# 03_SHIELD_SLOT_A.net
KiCad netlist of a schematic drawn in Altium Designer
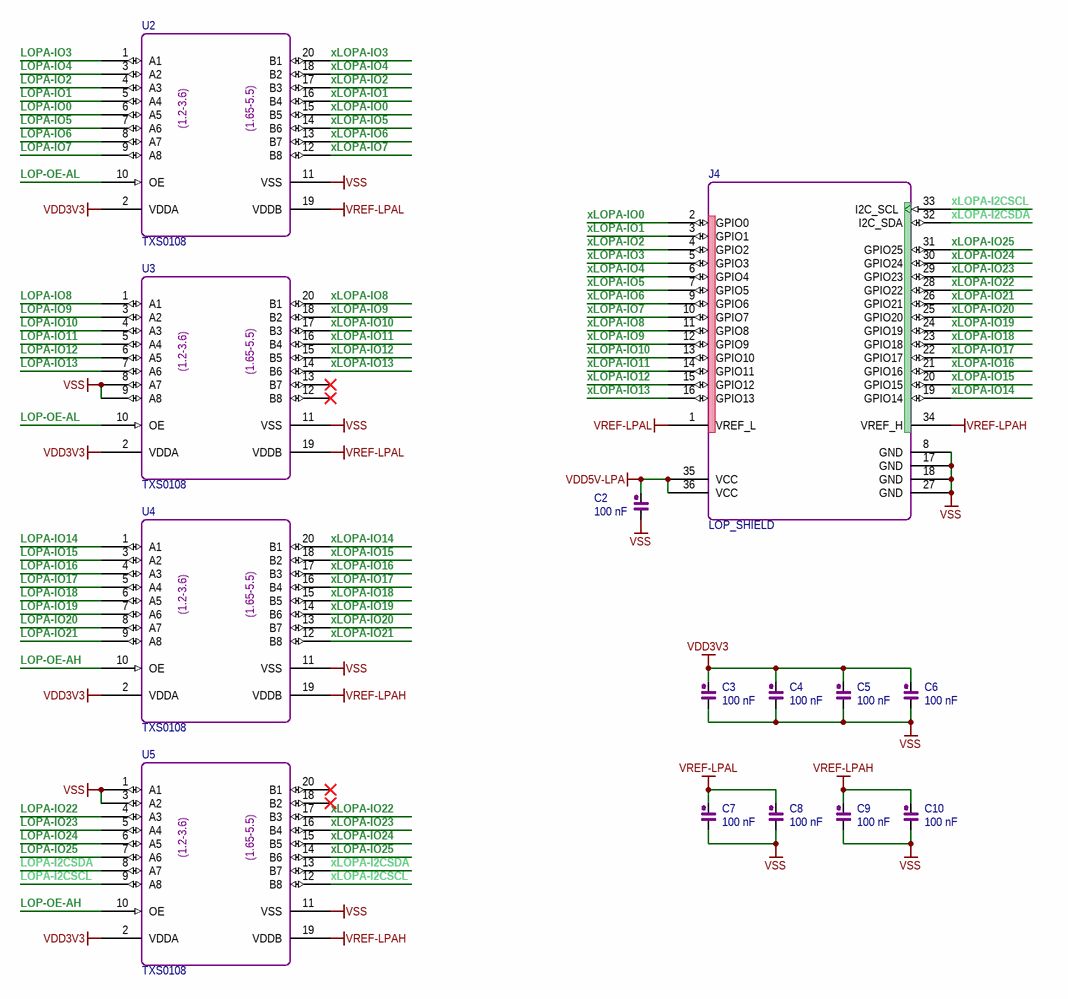
[diagram p0: 03_SHIELD_SLOT_A.SchDoc]

(export (version "E")
  (design (tool "Eeschema 10.0.6"))
  (components
    (comp (ref "C2")
      (value "100 nF")
      (footprint "0603A1")
      (description "Normal Capacitor")
      (fields
        (field (name "PARTNUMBER") "0")
        (field (name "PUBLISHER") "Cowin")
        (field (name "DESIGNER") "shyul")
      )
      (libsource (lib "Basc_1_Passive") (part "CAP"))
    )
    (comp (ref "C3")
      (value "100 nF")
      (footprint "0603A1")
      (description "Normal Capacitor")
      (fields
        (field (name "PARTNUMBER") "0")
        (field (name "PUBLISHER") "Cowin")
        (field (name "DESIGNER") "shyul")
      )
      (libsource (lib "Basc_1_Passive") (part "CAP"))
    )
    (comp (ref "C4")
      (value "100 nF")
      (footprint "0603A1")
      (description "Normal Capacitor")
      (fields
        (field (name "PARTNUMBER") "0")
        (field (name "PUBLISHER") "Cowin")
        (field (name "DESIGNER") "shyul")
      )
      (libsource (lib "Basc_1_Passive") (part "CAP"))
    )
    (comp (ref "C5")
      (value "100 nF")
      (footprint "0603A1")
      (description "Normal Capacitor")
      (fields
        (field (name "PARTNUMBER") "0")
        (field (name "PUBLISHER") "Cowin")
        (field (name "DESIGNER") "shyul")
      )
      (libsource (lib "Basc_1_Passive") (part "CAP"))
    )
    (comp (ref "C6")
      (value "100 nF")
      (footprint "0603A1")
      (description "Normal Capacitor")
      (fields
        (field (name "PARTNUMBER") "0")
        (field (name "PUBLISHER") "Cowin")
        (field (name "DESIGNER") "shyul")
      )
      (libsource (lib "Basc_1_Passive") (part "CAP"))
    )
    (comp (ref "C7")
      (value "100 nF")
      (footprint "0603A1")
      (description "Normal Capacitor")
      (fields
        (field (name "PARTNUMBER") "0")
        (field (name "PUBLISHER") "Cowin")
        (field (name "DESIGNER") "shyul")
      )
      (libsource (lib "Basc_1_Passive") (part "CAP"))
    )
    (comp (ref "C8")
      (value "100 nF")
      (footprint "0603A1")
      (description "Normal Capacitor")
      (fields
        (field (name "PARTNUMBER") "0")
        (field (name "PUBLISHER") "Cowin")
        (field (name "DESIGNER") "shyul")
      )
      (libsource (lib "Basc_1_Passive") (part "CAP"))
    )
    (comp (ref "C9")
      (value "100 nF")
      (footprint "0603A1")
      (description "Normal Capacitor")
      (fields
        (field (name "PARTNUMBER") "0")
        (field (name "PUBLISHER") "Cowin")
        (field (name "DESIGNER") "shyul")
      )
      (libsource (lib "Basc_1_Passive") (part "CAP"))
    )
    (comp (ref "C10")
      (value "100 nF")
      (footprint "0603A1")
      (description "Normal Capacitor")
      (fields
        (field (name "PARTNUMBER") "0")
        (field (name "PUBLISHER") "Cowin")
        (field (name "DESIGNER") "shyul")
      )
      (libsource (lib "Basc_1_Passive") (part "CAP"))
    )
    (comp (ref "J4")
      (value "LOP_SHIELD")
      (footprint "LOP_SHIELD")
      (description "Lophilo Shield Module Slot")
      (fields (field (name "PUBLISHER") "Cowin") (field (name "DESIGNER") "shyul"))
      (libsource (lib "PCB_LDB-U01") (part "LOP_SHIELD"))
    )
    (comp (ref "U2")
      (value "TXS0108")
      (footprint "TSSOP-20")
      (description "8-bit Translator")
      (fields (field (name "DESIGNER") "shyul") (field (name "PUBLISHER") "Cowin"))
      (libsource (lib "IC_01_Logic") (part "TXS0108"))
    )
    (comp (ref "U3")
      (value "TXS0108")
      (footprint "TSSOP-20")
      (description "8-bit Translator")
      (fields (field (name "DESIGNER") "shyul") (field (name "PUBLISHER") "Cowin"))
      (libsource (lib "IC_01_Logic") (part "TXS0108"))
    )
    (comp (ref "U4")
      (value "TXS0108")
      (footprint "TSSOP-20")
      (description "8-bit Translator")
      (fields (field (name "DESIGNER") "shyul") (field (name "PUBLISHER") "Cowin"))
      (libsource (lib "IC_01_Logic") (part "TXS0108"))
    )
    (comp (ref "U5")
      (value "TXS0108")
      (footprint "TSSOP-20")
      (description "8-bit Translator")
      (fields (field (name "DESIGNER") "shyul") (field (name "PUBLISHER") "Cowin"))
      (libsource (lib "IC_01_Logic") (part "TXS0108"))
    )
  )
  (nets
    (net (code "1") (name "/LOP-OE-AH") (class "Default")
      (node (ref "U4") (pin "10") (pinfunction "OE_10") (pintype "input"))
      (node (ref "U5") (pin "10") (pinfunction "OE_10") (pintype "input"))
    )
    (net (code "2") (name "/LOP-OE-AL") (class "Default")
      (node (ref "U2") (pin "10") (pinfunction "OE_10") (pintype "input"))
      (node (ref "U3") (pin "10") (pinfunction "OE_10") (pintype "input"))
    )
    (net (code "3") (name "/LOPA-I2CSCL") (class "Default")
      (node (ref "U5") (pin "9") (pinfunction "A8_9") (pintype "bidirectional"))
    )
    (net (code "4") (name "/LOPA-I2CSDA") (class "Default")
      (node (ref "U5") (pin "8") (pinfunction "A7_8") (pintype "bidirectional"))
    )
    (net (code "5") (name "/LOPA-IO0") (class "Default")
      (node (ref "U2") (pin "6") (pinfunction "A5_6") (pintype "bidirectional"))
    )
    (net (code "6") (name "/LOPA-IO1") (class "Default")
      (node (ref "U2") (pin "5") (pinfunction "A4_5") (pintype "bidirectional"))
    )
    (net (code "7") (name "/LOPA-IO2") (class "Default")
      (node (ref "U2") (pin "4") (pinfunction "A3_4") (pintype "bidirectional"))
    )
    (net (code "8") (name "/LOPA-IO3") (class "Default")
      (node (ref "U2") (pin "1") (pinfunction "A1_1") (pintype "bidirectional"))
    )
    (net (code "9") (name "/LOPA-IO4") (class "Default")
      (node (ref "U2") (pin "3") (pinfunction "A2_3") (pintype "bidirectional"))
    )
    (net (code "10") (name "/LOPA-IO5") (class "Default")
      (node (ref "U2") (pin "7") (pinfunction "A6_7") (pintype "bidirectional"))
    )
    (net (code "11") (name "/LOPA-IO6") (class "Default")
      (node (ref "U2") (pin "8") (pinfunction "A7_8") (pintype "bidirectional"))
    )
    (net (code "12") (name "/LOPA-IO7") (class "Default")
      (node (ref "U2") (pin "9") (pinfunction "A8_9") (pintype "bidirectional"))
    )
    (net (code "13") (name "/LOPA-IO8") (class "Default")
      (node (ref "U3") (pin "1") (pinfunction "A1_1") (pintype "bidirectional"))
    )
    (net (code "14") (name "/LOPA-IO9") (class "Default")
      (node (ref "U3") (pin "3") (pinfunction "A2_3") (pintype "bidirectional"))
    )
    (net (code "15") (name "/LOPA-IO10") (class "Default")
      (node (ref "U3") (pin "4") (pinfunction "A3_4") (pintype "bidirectional"))
    )
    (net (code "16") (name "/LOPA-IO11") (class "Default")
      (node (ref "U3") (pin "5") (pinfunction "A4_5") (pintype "bidirectional"))
    )
    (net (code "17") (name "/LOPA-IO12") (class "Default")
      (node (ref "U3") (pin "6") (pinfunction "A5_6") (pintype "bidirectional"))
    )
    (net (code "18") (name "/LOPA-IO13") (class "Default")
      (node (ref "U3") (pin "7") (pinfunction "A6_7") (pintype "bidirectional"))
    )
    (net (code "19") (name "/LOPA-IO14") (class "Default")
      (node (ref "U4") (pin "1") (pinfunction "A1_1") (pintype "bidirectional"))
    )
    (net (code "20") (name "/LOPA-IO15") (class "Default")
      (node (ref "U4") (pin "3") (pinfunction "A2_3") (pintype "bidirectional"))
    )
    (net (code "21") (name "/LOPA-IO16") (class "Default")
      (node (ref "U4") (pin "4") (pinfunction "A3_4") (pintype "bidirectional"))
    )
    (net (code "22") (name "/LOPA-IO17") (class "Default")
      (node (ref "U4") (pin "5") (pinfunction "A4_5") (pintype "bidirectional"))
    )
    (net (code "23") (name "/LOPA-IO18") (class "Default")
      (node (ref "U4") (pin "6") (pinfunction "A5_6") (pintype "bidirectional"))
    )
    (net (code "24") (name "/LOPA-IO19") (class "Default")
      (node (ref "U4") (pin "7") (pinfunction "A6_7") (pintype "bidirectional"))
    )
    (net (code "25") (name "/LOPA-IO20") (class "Default")
      (node (ref "U4") (pin "8") (pinfunction "A7_8") (pintype "bidirectional"))
    )
    (net (code "26") (name "/LOPA-IO21") (class "Default")
      (node (ref "U4") (pin "9") (pinfunction "A8_9") (pintype "bidirectional"))
    )
    (net (code "27") (name "/LOPA-IO22") (class "Default")
      (node (ref "U5") (pin "4") (pinfunction "A3_4") (pintype "bidirectional"))
    )
    (net (code "28") (name "/LOPA-IO23") (class "Default")
      (node (ref "U5") (pin "5") (pinfunction "A4_5") (pintype "bidirectional"))
    )
    (net (code "29") (name "/LOPA-IO24") (class "Default")
      (node (ref "U5") (pin "6") (pinfunction "A5_6") (pintype "bidirectional"))
    )
    (net (code "30") (name "/LOPA-IO25") (class "Default")
      (node (ref "U5") (pin "7") (pinfunction "A6_7") (pintype "bidirectional"))
    )
    (net (code "31") (name "/xLOPA-I2CSCL") (class "Default")
      (node (ref "J4") (pin "33") (pinfunction "I2C_SCL_33") (pintype "input"))
      (node (ref "U5") (pin "12") (pinfunction "B8_12") (pintype "bidirectional"))
    )
    (net (code "32") (name "/xLOPA-I2CSDA") (class "Default")
      (node (ref "J4") (pin "32") (pinfunction "I2C_SDA_32") (pintype "bidirectional"))
      (node (ref "U5") (pin "13") (pinfunction "B7_13") (pintype "bidirectional"))
    )
    (net (code "33") (name "/xLOPA-IO0") (class "Default")
      (node (ref "J4") (pin "2") (pinfunction "GPIO0_2") (pintype "bidirectional"))
      (node (ref "U2") (pin "15") (pinfunction "B5_15") (pintype "bidirectional"))
    )
    (net (code "34") (name "/xLOPA-IO1") (class "Default")
      (node (ref "J4") (pin "3") (pinfunction "GPIO1_3") (pintype "bidirectional"))
      (node (ref "U2") (pin "16") (pinfunction "B4_16") (pintype "bidirectional"))
    )
    (net (code "35") (name "/xLOPA-IO2") (class "Default")
      (node (ref "J4") (pin "4") (pinfunction "GPIO2_4") (pintype "bidirectional"))
      (node (ref "U2") (pin "17") (pinfunction "B3_17") (pintype "bidirectional"))
    )
    (net (code "36") (name "/xLOPA-IO3") (class "Default")
      (node (ref "J4") (pin "5") (pinfunction "GPIO3_5") (pintype "bidirectional"))
      (node (ref "U2") (pin "20") (pinfunction "B1_20") (pintype "bidirectional"))
    )
    (net (code "37") (name "/xLOPA-IO4") (class "Default")
      (node (ref "J4") (pin "6") (pinfunction "GPIO4_6") (pintype "bidirectional"))
      (node (ref "U2") (pin "18") (pinfunction "B2_18") (pintype "bidirectional"))
    )
    (net (code "38") (name "/xLOPA-IO5") (class "Default")
      (node (ref "J4") (pin "7") (pinfunction "GPIO5_7") (pintype "bidirectional"))
      (node (ref "U2") (pin "14") (pinfunction "B6_14") (pintype "bidirectional"))
    )
    (net (code "39") (name "/xLOPA-IO6") (class "Default")
      (node (ref "J4") (pin "9") (pinfunction "GPIO6_9") (pintype "bidirectional"))
      (node (ref "U2") (pin "13") (pinfunction "B7_13") (pintype "bidirectional"))
    )
    (net (code "40") (name "/xLOPA-IO7") (class "Default")
      (node (ref "J4") (pin "10") (pinfunction "GPIO7_10") (pintype "bidirectional"))
      (node (ref "U2") (pin "12") (pinfunction "B8_12") (pintype "bidirectional"))
    )
    (net (code "41") (name "/xLOPA-IO8") (class "Default")
      (node (ref "J4") (pin "11") (pinfunction "GPIO8_11") (pintype "bidirectional"))
      (node (ref "U3") (pin "20") (pinfunction "B1_20") (pintype "bidirectional"))
    )
    (net (code "42") (name "/xLOPA-IO9") (class "Default")
      (node (ref "J4") (pin "12") (pinfunction "GPIO9_12") (pintype "bidirectional"))
      (node (ref "U3") (pin "18") (pinfunction "B2_18") (pintype "bidirectional"))
    )
    (net (code "43") (name "/xLOPA-IO10") (class "Default")
      (node (ref "J4") (pin "13") (pinfunction "GPIO10_13") (pintype "bidirectional"))
      (node (ref "U3") (pin "17") (pinfunction "B3_17") (pintype "bidirectional"))
    )
    (net (code "44") (name "/xLOPA-IO11") (class "Default")
      (node (ref "J4") (pin "14") (pinfunction "GPIO11_14") (pintype "bidirectional"))
      (node (ref "U3") (pin "16") (pinfunction "B4_16") (pintype "bidirectional"))
    )
    (net (code "45") (name "/xLOPA-IO12") (class "Default")
      (node (ref "J4") (pin "15") (pinfunction "GPIO12_15") (pintype "bidirectional"))
      (node (ref "U3") (pin "15") (pinfunction "B5_15") (pintype "bidirectional"))
    )
    (net (code "46") (name "/xLOPA-IO13") (class "Default")
      (node (ref "J4") (pin "16") (pinfunction "GPIO13_16") (pintype "bidirectional"))
      (node (ref "U3") (pin "14") (pinfunction "B6_14") (pintype "bidirectional"))
    )
    (net (code "47") (name "/xLOPA-IO14") (class "Default")
      (node (ref "J4") (pin "19") (pinfunction "GPIO14_19") (pintype "bidirectional"))
      (node (ref "U4") (pin "20") (pinfunction "B1_20") (pintype "bidirectional"))
    )
    (net (code "48") (name "/xLOPA-IO15") (class "Default")
      (node (ref "J4") (pin "20") (pinfunction "GPIO15_20") (pintype "bidirectional"))
      (node (ref "U4") (pin "18") (pinfunction "B2_18") (pintype "bidirectional"))
    )
    (net (code "49") (name "/xLOPA-IO16") (class "Default")
      (node (ref "J4") (pin "21") (pinfunction "GPIO16_21") (pintype "bidirectional"))
      (node (ref "U4") (pin "17") (pinfunction "B3_17") (pintype "bidirectional"))
    )
    (net (code "50") (name "/xLOPA-IO17") (class "Default")
      (node (ref "J4") (pin "22") (pinfunction "GPIO17_22") (pintype "bidirectional"))
      (node (ref "U4") (pin "16") (pinfunction "B4_16") (pintype "bidirectional"))
    )
    (net (code "51") (name "/xLOPA-IO18") (class "Default")
      (node (ref "J4") (pin "23") (pinfunction "GPIO18_23") (pintype "bidirectional"))
      (node (ref "U4") (pin "15") (pinfunction "B5_15") (pintype "bidirectional"))
    )
    (net (code "52") (name "/xLOPA-IO19") (class "Default")
      (node (ref "J4") (pin "24") (pinfunction "GPIO19_24") (pintype "bidirectional"))
      (node (ref "U4") (pin "14") (pinfunction "B6_14") (pintype "bidirectional"))
    )
    (net (code "53") (name "/xLOPA-IO20") (class "Default")
      (node (ref "J4") (pin "25") (pinfunction "GPIO20_25") (pintype "bidirectional"))
      (node (ref "U4") (pin "13") (pinfunction "B7_13") (pintype "bidirectional"))
    )
    (net (code "54") (name "/xLOPA-IO21") (class "Default")
      (node (ref "J4") (pin "26") (pinfunction "GPIO21_26") (pintype "bidirectional"))
      (node (ref "U4") (pin "12") (pinfunction "B8_12") (pintype "bidirectional"))
    )
    (net (code "55") (name "/xLOPA-IO22") (class "Default")
      (node (ref "J4") (pin "28") (pinfunction "GPIO22_28") (pintype "bidirectional"))
      (node (ref "U5") (pin "17") (pinfunction "B3_17") (pintype "bidirectional"))
    )
    (net (code "56") (name "/xLOPA-IO23") (class "Default")
      (node (ref "J4") (pin "29") (pinfunction "GPIO23_29") (pintype "bidirectional"))
      (node (ref "U5") (pin "16") (pinfunction "B4_16") (pintype "bidirectional"))
    )
    (net (code "57") (name "/xLOPA-IO24") (class "Default")
      (node (ref "J4") (pin "30") (pinfunction "GPIO24_30") (pintype "bidirectional"))
      (node (ref "U5") (pin "15") (pinfunction "B5_15") (pintype "bidirectional"))
    )
    (net (code "58") (name "/xLOPA-IO25") (class "Default")
      (node (ref "J4") (pin "31") (pinfunction "GPIO25_31") (pintype "bidirectional"))
      (node (ref "U5") (pin "14") (pinfunction "B6_14") (pintype "bidirectional"))
    )
    (net (code "59") (name "VDD3V3") (class "Default")
      (node (ref "C3") (pin "2") (pinfunction "2_2") (pintype "passive"))
      (node (ref "C4") (pin "2") (pinfunction "2_2") (pintype "passive"))
      (node (ref "C5") (pin "2") (pinfunction "2_2") (pintype "passive"))
      (node (ref "C6") (pin "2") (pinfunction "2_2") (pintype "passive"))
      (node (ref "U2") (pin "2") (pinfunction "VDDA_2") (pintype "power_in"))
      (node (ref "U3") (pin "2") (pinfunction "VDDA_2") (pintype "power_in"))
      (node (ref "U4") (pin "2") (pinfunction "VDDA_2") (pintype "power_in"))
      (node (ref "U5") (pin "2") (pinfunction "VDDA_2") (pintype "power_in"))
    )
    (net (code "60") (name "VDD5V-LPA") (class "Default")
      (node (ref "C2") (pin "2") (pinfunction "2_2") (pintype "passive"))
      (node (ref "J4") (pin "35") (pinfunction "VCC_35") (pintype "passive"))
      (node (ref "J4") (pin "36") (pinfunction "VCC_36") (pintype "passive"))
    )
    (net (code "61") (name "VREF-LPAH") (class "Default")
      (node (ref "C10") (pin "2") (pinfunction "2_2") (pintype "passive"))
      (node (ref "C9") (pin "2") (pinfunction "2_2") (pintype "passive"))
      (node (ref "J4") (pin "34") (pinfunction "VREF_H_34") (pintype "power_in"))
      (node (ref "U4") (pin "19") (pinfunction "VDDB_19") (pintype "power_in"))
      (node (ref "U5") (pin "19") (pinfunction "VDDB_19") (pintype "power_in"))
    )
    (net (code "62") (name "VREF-LPAL") (class "Default")
      (node (ref "C7") (pin "2") (pinfunction "2_2") (pintype "passive"))
      (node (ref "C8") (pin "2") (pinfunction "2_2") (pintype "passive"))
      (node (ref "J4") (pin "1") (pinfunction "VREF_L_1") (pintype "power_in"))
      (node (ref "U2") (pin "19") (pinfunction "VDDB_19") (pintype "power_in"))
      (node (ref "U3") (pin "19") (pinfunction "VDDB_19") (pintype "power_in"))
    )
    (net (code "63") (name "VSS") (class "Default")
      (node (ref "C10") (pin "1") (pinfunction "1_1") (pintype "passive"))
      (node (ref "C2") (pin "1") (pinfunction "1_1") (pintype "passive"))
      (node (ref "C3") (pin "1") (pinfunction "1_1") (pintype "passive"))
      (node (ref "C4") (pin "1") (pinfunction "1_1") (pintype "passive"))
      (node (ref "C5") (pin "1") (pinfunction "1_1") (pintype "passive"))
      (node (ref "C6") (pin "1") (pinfunction "1_1") (pintype "passive"))
      (node (ref "C7") (pin "1") (pinfunction "1_1") (pintype "passive"))
      (node (ref "C8") (pin "1") (pinfunction "1_1") (pintype "passive"))
      (node (ref "C9") (pin "1") (pinfunction "1_1") (pintype "passive"))
      (node (ref "J4") (pin "17") (pinfunction "GND_17") (pintype "passive"))
      (node (ref "J4") (pin "18") (pinfunction "GND_18") (pintype "passive"))
      (node (ref "J4") (pin "27") (pinfunction "GND_27") (pintype "passive"))
      (node (ref "J4") (pin "8") (pinfunction "GND_8") (pintype "passive"))
      (node (ref "U2") (pin "11") (pinfunction "VSS_11") (pintype "passive"))
      (node (ref "U3") (pin "11") (pinfunction "VSS_11") (pintype "passive"))
      (node (ref "U3") (pin "8") (pinfunction "A7_8") (pintype "bidirectional"))
      (node (ref "U3") (pin "9") (pinfunction "A8_9") (pintype "bidirectional"))
      (node (ref "U4") (pin "11") (pinfunction "VSS_11") (pintype "passive"))
      (node (ref "U5") (pin "1") (pinfunction "A1_1") (pintype "bidirectional"))
      (node (ref "U5") (pin "11") (pinfunction "VSS_11") (pintype "passive"))
      (node (ref "U5") (pin "3") (pinfunction "A2_3") (pintype "bidirectional"))
    )
    (net (code "64") (name "unconnected-(U3-B7-Pad13)") (class "Default")
      (node (ref "U3") (pin "13") (pinfunction "B7_13") (pintype "bidirectional+no_connect"))
    )
    (net (code "65") (name "unconnected-(U3-B8-Pad12)") (class "Default")
      (node (ref "U3") (pin "12") (pinfunction "B8_12") (pintype "bidirectional+no_connect"))
    )
    (net (code "66") (name "unconnected-(U5-B1-Pad20)") (class "Default")
      (node (ref "U5") (pin "20") (pinfunction "B1_20") (pintype "bidirectional+no_connect"))
    )
    (net (code "67") (name "unconnected-(U5-B2-Pad18)") (class "Default")
      (node (ref "U5") (pin "18") (pinfunction "B2_18") (pintype "bidirectional+no_connect"))
    )
  )
)
